# SH3_-_USB.net
KiCad netlist of a schematic drawn in Altium Designer
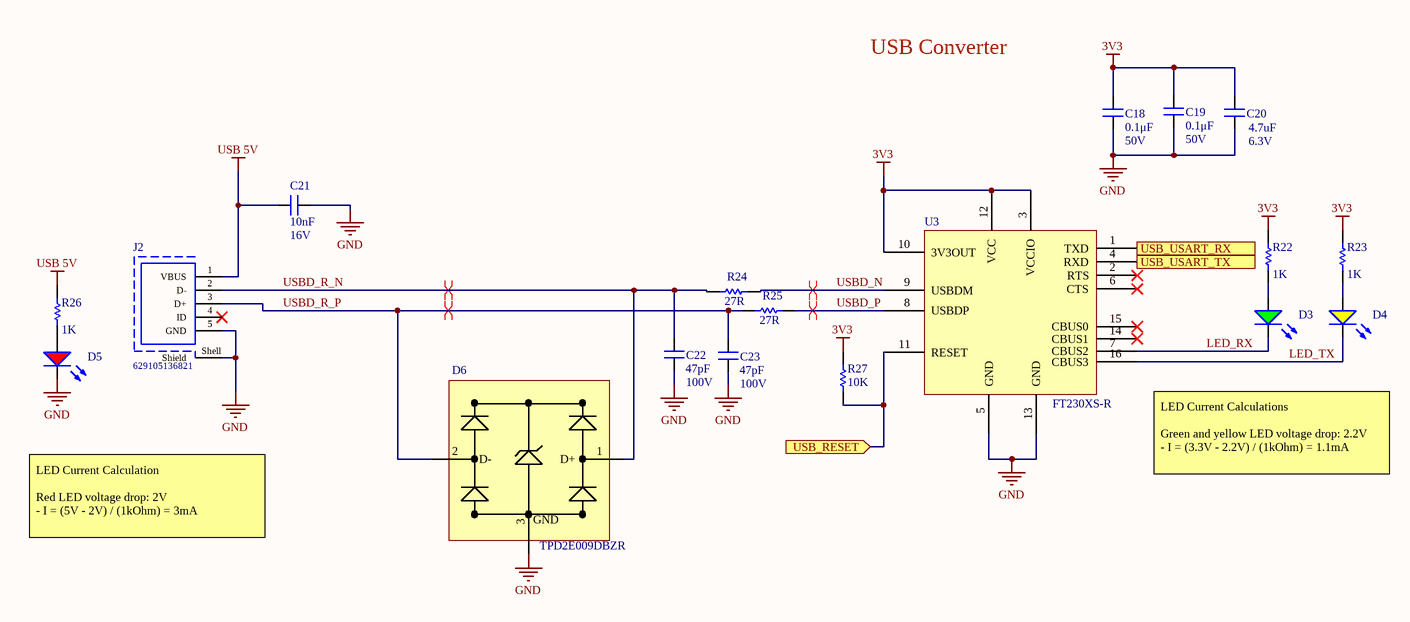
[diagram p0: SH3 - USB.SchDoc]

(export (version "E")
  (design (tool "Eeschema 10.0.6"))
  (components
    (comp (ref "C18")
      (value "0.1μF")
      (footprint "CAP2012")
      (description "CAP CER 0.1UF 50V X7R 0805")
      (fields
        (field (name "TOLERANCE") "10%")
        (field (name "VOLTAGE RATING") "50V")
        (field (name "Comment") "CAP_0.1uF_50V_0805")
      )
      (libsource (lib "UWRT_Schematic_Library_2020") (part "CAP_0.1uF_50V_0805"))
    )
    (comp (ref "C19")
      (value "0.1μF")
      (footprint "CAP2012")
      (description "CAP CER 0.1UF 50V X7R 0805")
      (fields
        (field (name "TOLERANCE") "10%")
        (field (name "VOLTAGE RATING") "50V")
        (field (name "Comment") "CAP_0.1uF_50V_0805")
      )
      (libsource (lib "UWRT_Schematic_Library_2020") (part "CAP_0.1uF_50V_0805"))
    )
    (comp (ref "C20")
      (value "4.7uF")
      (footprint "CAPC0603(1608)55_N")
      (description "CAP CER 4.7UF 6.3V X5R 0603")
      (fields (field (name "VOLTAGE RATING") "6.3V") (field (name "Comment") "CAP_4.7uF_0603"))
      (libsource (lib "UWRT_Schematic_Library_2020") (part "CAP_4.7uF_0603"))
    )
    (comp (ref "C21")
      (value "10nF")
      (footprint "CAP0603")
      (description "CAP CER 10000PF 16V X7R 0603")
      (fields (field (name "VOLTAGE RATING") "16V") (field (name "Comment") "CAP_10nF_0603"))
      (libsource (lib "UWRT_Schematic_Library_2020") (part "CAP_10nF_0603"))
    )
    (comp (ref "C22")
      (value "47pF")
      (footprint "CAP0603")
      (description "CAP CER 47PF 100V C0G/NP0 0603")
      (fields (field (name "VOLTAGE RATING") "100V") (field (name "Comment") "CAP_47pF_100V_0603"))
      (libsource (lib "UWRT_Schematic_Library_2020") (part "CAP_47pF_100V_0603"))
    )
    (comp (ref "C23")
      (value "47pF")
      (footprint "CAP0603")
      (description "CAP CER 47PF 100V C0G/NP0 0603")
      (fields (field (name "VOLTAGE RATING") "100V") (field (name "Comment") "CAP_47pF_100V_0603"))
      (libsource (lib "UWRT_Schematic_Library_2020") (part "CAP_47pF_100V_0603"))
    )
    (comp (ref "D3")
      (value "LG R971-KN-1")
      (footprint "LED_0805_GREEN")
      (description "LED GREEN DIFFUSED 0805 SMD")
      (libsource (lib "UWRT_Schematic_Library_2020") (part "DIO_LED_G"))
    )
    (comp (ref "D4")
      (value "LY R976-PS-36")
      (footprint "LED_0805_YELLOW")
      (description "LED YELLOW DIFFUSED 0805 SMD")
      (libsource (lib "UWRT_Schematic_Library_2020") (part "DIO_LED_Y"))
    )
    (comp (ref "D5")
      (value "LS R976-NR-1")
      (footprint "LED_0805_RED")
      (description "LED RED DIFFUSED 0805 SMD")
      (libsource (lib "UWRT_Schematic_Library_2020") (part "DIO_LED_R"))
    )
    (comp (ref "D6")
      (value "TVS_DIODE_USB_5.5V")
      (footprint "SOT23-3")
      (description "TVS DIODE 5.5V 8V SOT23-3")
      (fields
        (field (name "MANUFACTURER") "Texas Instruments")
        (field (name "MANUFACTURER PART NUMBER") "TPD2E009DBZR")
      )
      (libsource (lib "UWRT_Schematic_Library_2020") (part "TVS_DIODE_USB_5.5V"))
    )
    (comp (ref "J2")
      (value "629105136821")
      (footprint "629105136821")
      (description "CONN RCPT USB2.0 MICRO B SMD R/A")
      (fields (field (name "MANUFACTURER") "Wurth Elektronik") (field (name "PUBLISHER") "WurthElektronik"))
      (libsource (lib "UWRT_Schematic_Library_2020") (part "WE 629105136821"))
    )
    (comp (ref "R22")
      (value "1K")
      (footprint "RESC0603(1608)_N")
      (description "RES SMD 1K OHM 5% 1/10W 0603")
      (fields (field (name "TOLERANCE") "5%") (field (name "Comment") "RES_1K_0603"))
      (libsource (lib "UWRT_Schematic_Library_2020") (part "RES_1K_0603"))
    )
    (comp (ref "R23")
      (value "1K")
      (footprint "RESC0603(1608)_N")
      (description "RES SMD 1K OHM 5% 1/10W 0603")
      (fields (field (name "TOLERANCE") "5%") (field (name "Comment") "RES_1K_0603"))
      (libsource (lib "UWRT_Schematic_Library_2020") (part "RES_1K_0603"))
    )
    (comp (ref "R24")
      (value "RES_27R_0603")
      (footprint "RESC0603(1608)_N")
      (description "RES SMD 27 OHM 5% 1/10W 0603")
      (fields
        (field (name "MANUFACTURER") "Yageo")
        (field (name "MANUFACTURER PART NUMBER") "RC0603JR-0727RL")
        (field (name "RESISTANCE") "27R")
      )
      (libsource (lib "UWRT_Schematic_Library_2020") (part "RES_27R_0603"))
    )
    (comp (ref "R25")
      (value "RES_27R_0603")
      (footprint "RESC0603(1608)_N")
      (description "RES SMD 27 OHM 5% 1/10W 0603")
      (fields
        (field (name "MANUFACTURER") "Yageo")
        (field (name "MANUFACTURER PART NUMBER") "RC0603JR-0727RL")
        (field (name "RESISTANCE") "27R")
      )
      (libsource (lib "UWRT_Schematic_Library_2020") (part "RES_27R_0603"))
    )
    (comp (ref "R26")
      (value "1K")
      (footprint "RESC0603(1608)_N")
      (description "RES SMD 1K OHM 5% 1/10W 0603")
      (fields (field (name "TOLERANCE") "5%") (field (name "Comment") "RES_1K_0603"))
      (libsource (lib "UWRT_Schematic_Library_2020") (part "RES_1K_0603"))
    )
    (comp (ref "R27")
      (value "10K")
      (footprint "RESC0603(1608)_N")
      (description "RES SMD 10K OHM 5% 1/10W 0603")
      (fields (field (name "TOLERANCE") "5%") (field (name "Comment") "RES_10K_0603"))
      (libsource (lib "UWRT_Schematic_Library_2020") (part "RES_10K_0603"))
    )
    (comp (ref "U3")
      (value "IC_USB_TRANSCEIVER")
      (footprint "SSOP16-0.635-5X4MM")
      (description "IC USB SERIAL BASIC UART 16SSOP")
      (fields (field (name "MANUFACTURER PART NUMBER 1") "FT230XS-R"))
      (libsource (lib "UWRT_Schematic_Library_2020") (part "IC_USB_TRANSCEIVER"))
    )
  )
  (nets
    (net (code "1") (name "/LED_RX") (class "Default")
      (node (ref "D3") (pin "2") (pinfunction "K_2") (pintype "passive"))
      (node (ref "U3") (pin "7") (pinfunction "CBUS2_7") (pintype "passive"))
    )
    (net (code "2") (name "/LED_TX") (class "Default")
      (node (ref "D4") (pin "2") (pinfunction "K_2") (pintype "passive"))
      (node (ref "U3") (pin "16") (pinfunction "CBUS3_16") (pintype "passive"))
    )
    (net (code "3") (name "/USBD_N") (class "Default")
      (node (ref "R24") (pin "2") (pinfunction "2_2") (pintype "passive"))
      (node (ref "U3") (pin "9") (pinfunction "USBDM_9") (pintype "passive"))
    )
    (net (code "4") (name "/USBD_P") (class "Default")
      (node (ref "R25") (pin "2") (pinfunction "2_2") (pintype "passive"))
      (node (ref "U3") (pin "8") (pinfunction "USBDP_8") (pintype "passive"))
    )
    (net (code "5") (name "/USBD_R_N") (class "Default")
      (node (ref "C22") (pin "2") (pinfunction "2_2") (pintype "passive"))
      (node (ref "D6") (pin "1") (pinfunction "D+_1") (pintype "passive"))
      (node (ref "J2") (pin "2") (pinfunction "D-_2") (pintype "passive"))
      (node (ref "R24") (pin "1") (pinfunction "1_1") (pintype "passive"))
    )
    (net (code "6") (name "/USBD_R_P") (class "Default")
      (node (ref "C23") (pin "1") (pinfunction "1_1") (pintype "passive"))
      (node (ref "D6") (pin "2") (pinfunction "D-_2") (pintype "passive"))
      (node (ref "J2") (pin "3") (pinfunction "D+_3") (pintype "passive"))
      (node (ref "R25") (pin "1") (pinfunction "1_1") (pintype "passive"))
    )
    (net (code "7") (name "/USB_RESET") (class "Default")
      (node (ref "R27") (pin "1") (pinfunction "1_1") (pintype "passive"))
      (node (ref "U3") (pin "11") (pinfunction "RESET_11") (pintype "passive"))
    )
    (net (code "8") (name "/USB_USART_RX") (class "Default")
      (node (ref "U3") (pin "1") (pinfunction "TXD_1") (pintype "passive"))
    )
    (net (code "9") (name "/USB_USART_TX") (class "Default")
      (node (ref "U3") (pin "4") (pinfunction "RXD_4") (pintype "passive"))
    )
    (net (code "10") (name "3V3") (class "Default")
      (node (ref "C18") (pin "2") (pinfunction "2_2") (pintype "passive"))
      (node (ref "C19") (pin "2") (pinfunction "2_2") (pintype "passive"))
      (node (ref "C20") (pin "1") (pinfunction "1_1") (pintype "passive"))
      (node (ref "R22") (pin "2") (pinfunction "2_2") (pintype "passive"))
      (node (ref "R23") (pin "2") (pinfunction "2_2") (pintype "passive"))
      (node (ref "R27") (pin "2") (pinfunction "2_2") (pintype "passive"))
      (node (ref "U3") (pin "10") (pinfunction "3V3OUT_10") (pintype "passive"))
      (node (ref "U3") (pin "12") (pinfunction "VCC_12") (pintype "passive"))
      (node (ref "U3") (pin "3") (pinfunction "VCCIO_3") (pintype "passive"))
    )
    (net (code "11") (name "GND") (class "Default")
      (node (ref "C18") (pin "1") (pinfunction "1_1") (pintype "passive"))
      (node (ref "C19") (pin "1") (pinfunction "1_1") (pintype "passive"))
      (node (ref "C20") (pin "2") (pinfunction "2_2") (pintype "passive"))
      (node (ref "C21") (pin "2") (pinfunction "2_2") (pintype "passive"))
      (node (ref "C22") (pin "1") (pinfunction "1_1") (pintype "passive"))
      (node (ref "C23") (pin "2") (pinfunction "2_2") (pintype "passive"))
      (node (ref "D5") (pin "2") (pinfunction "K_2") (pintype "passive"))
      (node (ref "D6") (pin "3") (pinfunction "GND_3") (pintype "passive"))
      (node (ref "J2") (pin "5") (pinfunction "GND_5") (pintype "passive"))
      (node (ref "J2") (pin "Shell") (pinfunction "Shield_Shell") (pintype "passive"))
      (node (ref "U3") (pin "13") (pinfunction "GND_13") (pintype "passive"))
      (node (ref "U3") (pin "5") (pinfunction "GND_5") (pintype "passive"))
    )
    (net (code "12") (name "Net-(D3-A)") (class "Default")
      (node (ref "D3") (pin "1") (pinfunction "A_1") (pintype "passive"))
      (node (ref "R22") (pin "1") (pinfunction "1_1") (pintype "passive"))
    )
    (net (code "13") (name "Net-(D4-A)") (class "Default")
      (node (ref "D4") (pin "1") (pinfunction "A_1") (pintype "passive"))
      (node (ref "R23") (pin "1") (pinfunction "1_1") (pintype "passive"))
    )
    (net (code "14") (name "Net-(D5-A)") (class "Default")
      (node (ref "D5") (pin "1") (pinfunction "A_1") (pintype "passive"))
      (node (ref "R26") (pin "1") (pinfunction "1_1") (pintype "passive"))
    )
    (net (code "15") (name "USB 5V") (class "Default")
      (node (ref "C21") (pin "1") (pinfunction "1_1") (pintype "passive"))
      (node (ref "J2") (pin "1") (pinfunction "VBUS_1") (pintype "passive"))
      (node (ref "R26") (pin "2") (pinfunction "2_2") (pintype "passive"))
    )
    (net (code "16") (name "unconnected-(J2-ID-Pad4)") (class "Default")
      (node (ref "J2") (pin "4") (pinfunction "ID_4") (pintype "passive+no_connect"))
    )
    (net (code "17") (name "unconnected-(U3-CBUS0-Pad15)") (class "Default")
      (node (ref "U3") (pin "15") (pinfunction "CBUS0_15") (pintype "passive+no_connect"))
    )
    (net (code "18") (name "unconnected-(U3-CBUS1-Pad14)") (class "Default")
      (node (ref "U3") (pin "14") (pinfunction "CBUS1_14") (pintype "passive+no_connect"))
    )
    (net (code "19") (name "unconnected-(U3-CTS-Pad6)") (class "Default")
      (node (ref "U3") (pin "6") (pinfunction "CTS_6") (pintype "passive+no_connect"))
    )
    (net (code "20") (name "unconnected-(U3-RTS-Pad2)") (class "Default")
      (node (ref "U3") (pin "2") (pinfunction "RTS_2") (pintype "passive+no_connect"))
    )
  )
)
